# MINI_SAM_D51_004.net
KiCad netlist of a schematic drawn in EAGLE
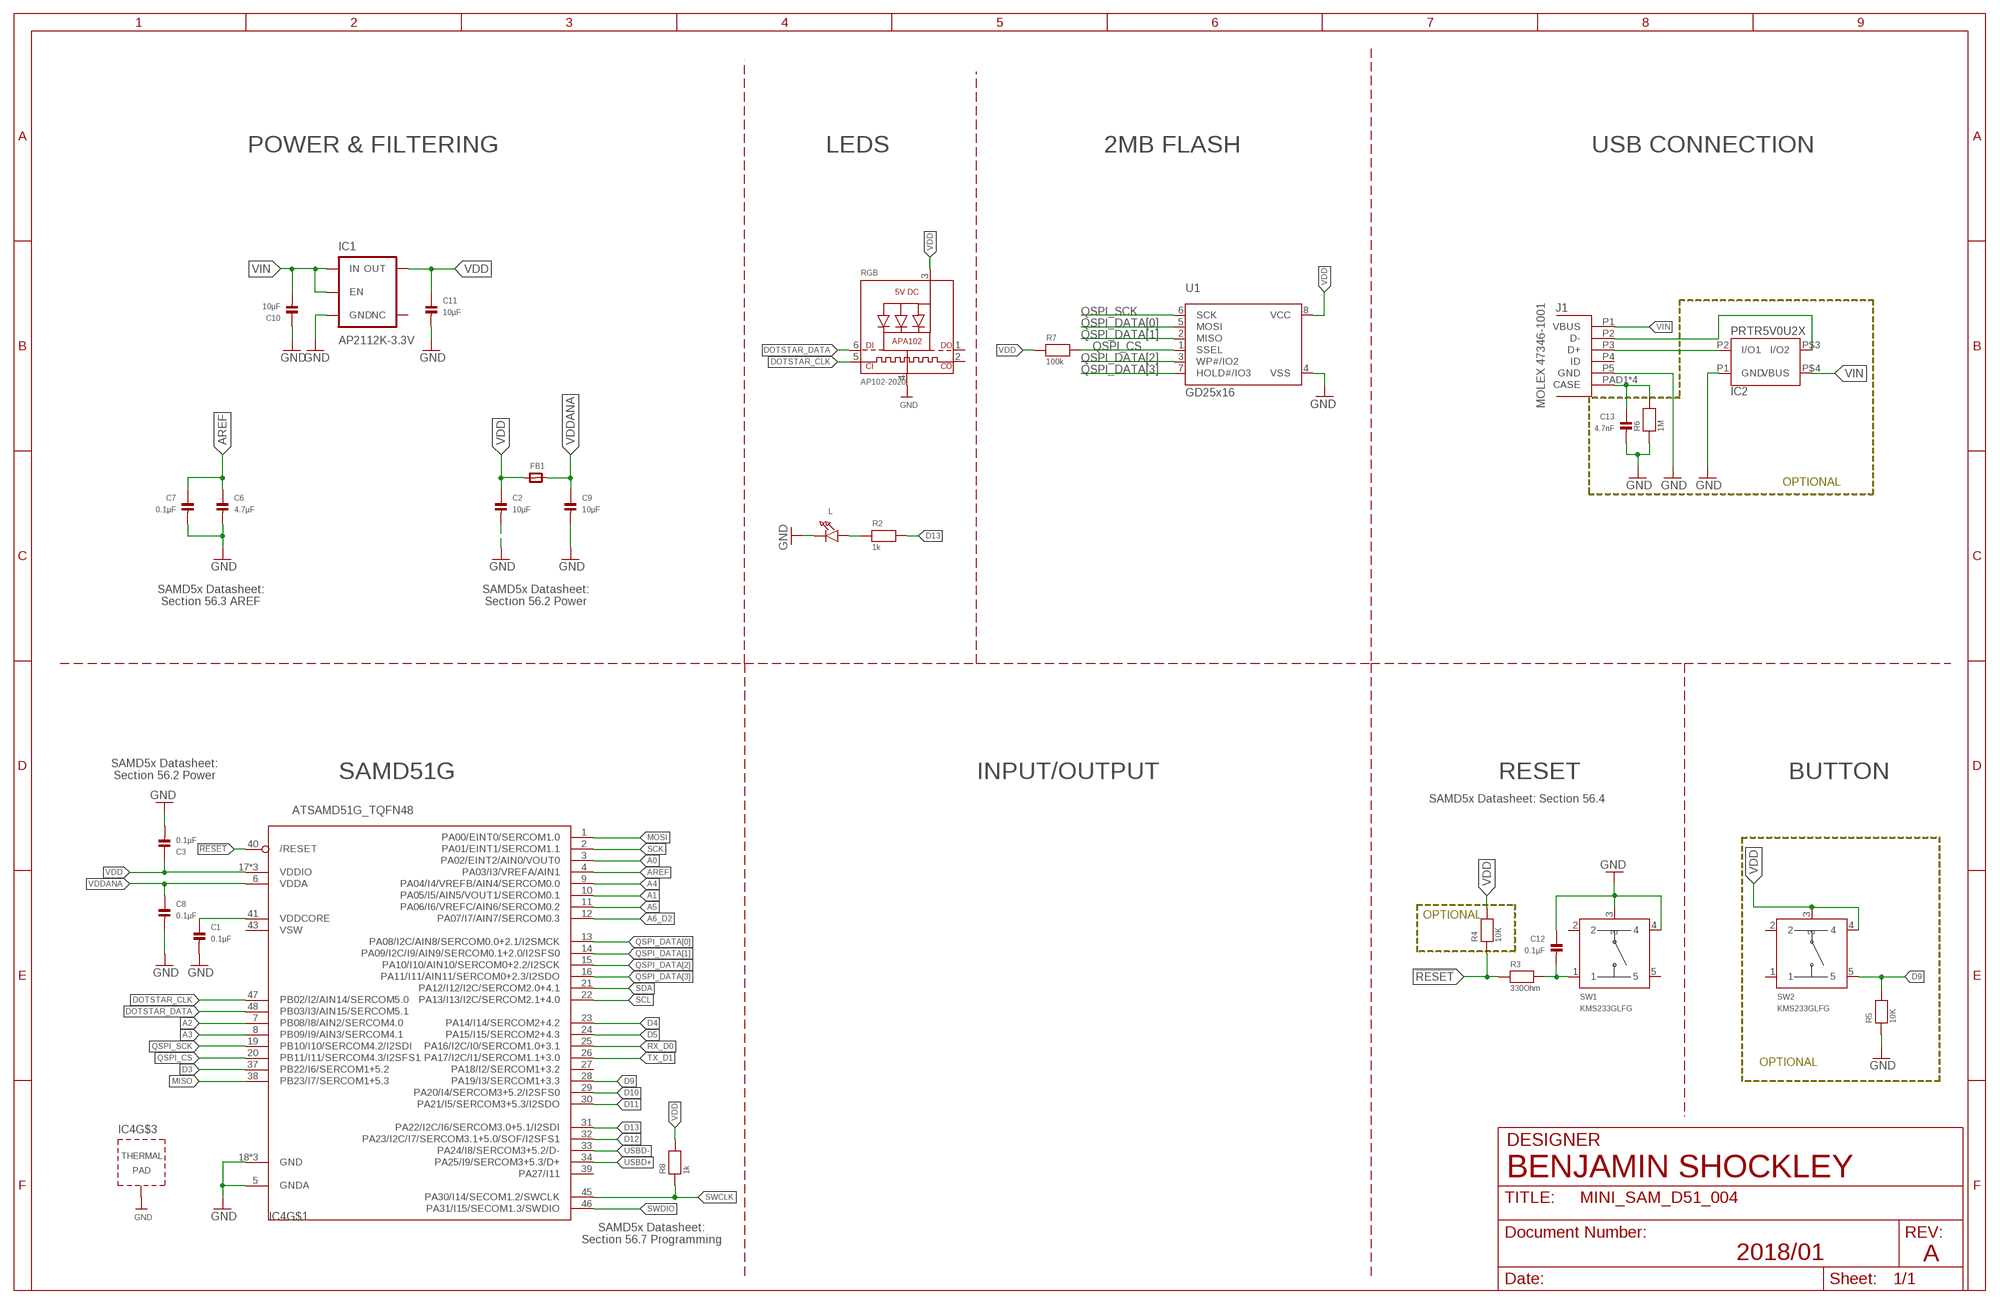
[diagram p0: schematic, sheet 1]

(export (version "E")
  (design (tool "Eeschema 10.0.6"))
  (components
    (comp (ref "C1")
      (value "0.1µF")
      (footprint "eagle-import:_0603MP")
      (libsource (lib "eagle-import") (part "CAP_CERAMIC_0603MP"))
    )
    (comp (ref "C2")
      (value "10µF")
      (footprint "eagle-import:_0603MP")
      (libsource (lib "eagle-import") (part "CAP_CERAMIC_0603MP"))
    )
    (comp (ref "C3")
      (value "0.1µF")
      (footprint "eagle-import:_0603MP")
      (libsource (lib "eagle-import") (part "CAP_CERAMIC_0603MP"))
    )
    (comp (ref "C6")
      (value "4.7µF")
      (footprint "eagle-import:_0603MP")
      (libsource (lib "eagle-import") (part "CAP_CERAMIC_0603MP"))
    )
    (comp (ref "C7")
      (value "0.1µF")
      (footprint "eagle-import:_0603MP")
      (libsource (lib "eagle-import") (part "CAP_CERAMIC_0603MP"))
    )
    (comp (ref "C8")
      (value "0.1µF")
      (footprint "eagle-import:_0603MP")
      (libsource (lib "eagle-import") (part "CAP_CERAMIC_0603MP"))
    )
    (comp (ref "C9")
      (value "10µF")
      (footprint "eagle-import:_0603MP")
      (libsource (lib "eagle-import") (part "CAP_CERAMIC_0603MP"))
    )
    (comp (ref "C10")
      (value "10µF")
      (footprint "eagle-import:_0603MP")
      (libsource (lib "eagle-import") (part "CAP_CERAMIC_0603MP"))
    )
    (comp (ref "C11")
      (value "10µF")
      (footprint "eagle-import:_0603MP")
      (libsource (lib "eagle-import") (part "CAP_CERAMIC_0603MP"))
    )
    (comp (ref "C12")
      (value "0.1µF")
      (footprint "eagle-import:_0603MP")
      (libsource (lib "eagle-import") (part "CAP_CERAMIC_0603MP"))
    )
    (comp (ref "C13")
      (value "4.7nF")
      (footprint "eagle-import:_0603MP")
      (libsource (lib "eagle-import") (part "CAP_CERAMIC_0603MP"))
    )
    (comp (ref "FB1")
      (value "FERRITE_0603MP")
      (footprint "eagle-import:_0603MP")
      (libsource (lib "eagle-import") (part "FERRITE_0603MP"))
    )
    (comp (ref "IC1")
      (value "AP2112K-3.3V")
      (footprint "eagle-import:SOT23-5")
      (libsource (lib "eagle-import") (part "V_REG_AP2112K-3.3V"))
    )
    (comp (ref "IC2")
      (value "PRTR5V0U2X")
      (footprint "eagle-import:SOT143B_REFLOW")
      (libsource (lib "eagle-import") (part "PRTR5V0U2X"))
    )
    (comp (ref "IC4")
      (value "ATSAMD51G_TQFN48")
      (footprint "eagle-import:TQFN48_7MM")
      (libsource (lib "eagle-import") (part "ATSAMD51G_TQFN48"))
    )
    (comp (ref "J1")
      (value "MOLEX_47346-100147346")
      (footprint "eagle-import:MOLEX_47346-1001")
      (libsource (lib "eagle-import") (part "MOLEX_47346-100147346"))
    )
    (comp (ref "L")
      (value "LED0603_NOOUTLINE")
      (footprint "eagle-import:CHIPLED_0603_NOOUTLINE")
      (libsource (lib "eagle-import") (part "LED0603_NOOUTLINE"))
    )
    (comp (ref "R2")
      (value "1k")
      (footprint "eagle-import:_0603MP")
      (libsource (lib "eagle-import") (part "RESISTOR_0603MP"))
    )
    (comp (ref "R3")
      (value "330Ohm")
      (footprint "eagle-import:_0603MP")
      (libsource (lib "eagle-import") (part "RESISTOR_0603MP"))
    )
    (comp (ref "R4")
      (value "10K")
      (footprint "eagle-import:_0603MP")
      (libsource (lib "eagle-import") (part "RESISTOR_0603MP"))
    )
    (comp (ref "R5")
      (value "10K")
      (footprint "eagle-import:_0603MP")
      (libsource (lib "eagle-import") (part "RESISTOR_0603MP"))
    )
    (comp (ref "R6")
      (value "1M")
      (footprint "eagle-import:_0603MP")
      (libsource (lib "eagle-import") (part "RESISTOR_0603MP"))
    )
    (comp (ref "R7")
      (value "100k")
      (footprint "eagle-import:_0603MP")
      (libsource (lib "eagle-import") (part "RESISTOR_0603MP"))
    )
    (comp (ref "R8")
      (value "1k")
      (footprint "eagle-import:_0603MP")
      (libsource (lib "eagle-import") (part "RESISTOR_0603MP"))
    )
    (comp (ref "RGB")
      (value "AP102-2020")
      (footprint "eagle-import:APA102_2020")
      (libsource (lib "eagle-import") (part "APA1022020"))
    )
    (comp (ref "SW1")
      (value "KMS233GLFG")
      (footprint "eagle-import:KMS_SWITCH")
      (libsource (lib "eagle-import") (part "KMS_SWITCHKMS"))
    )
    (comp (ref "SW2")
      (value "KMS233GLFG")
      (footprint "eagle-import:KMS_SWITCH")
      (libsource (lib "eagle-import") (part "KMS_SWITCHKMS"))
    )
    (comp (ref "U1")
      (value "GD25x16")
      (footprint "eagle-import:USON8")
      (libsource (lib "eagle-import") (part "SPIFLASH_8PINUX"))
    )
  )
  (nets
    (net (code "1") (name "/VSW") (class "Default")
      (node (ref "IC4") (pin "43") (pinfunction "VSW_43") (pintype "power_in"))
    )
    (net (code "2") (name "/~{RESET}") (class "Default")
      (node (ref "IC4") (pin "40") (pinfunction "/RESET_40") (pintype "bidirectional"))
      (node (ref "R3") (pin "1") (pinfunction "1_1") (pintype "passive"))
      (node (ref "R4") (pin "1") (pinfunction "1_1") (pintype "passive"))
    )
    (net (code "3") (name "A0") (class "Default")
      (node (ref "IC4") (pin "3") (pinfunction "PA02/EINT2/AIN0/VOUT0_3") (pintype "bidirectional"))
    )
    (net (code "4") (name "A1") (class "Default")
      (node (ref "IC4") (pin "10") (pinfunction "PA05/I5/AIN5/VOUT1/SERCOM0.1_10") (pintype "bidirectional"))
    )
    (net (code "5") (name "A2") (class "Default")
      (node (ref "IC4") (pin "7") (pinfunction "PB08/I8/AIN2/SERCOM4.0_7") (pintype "bidirectional"))
    )
    (net (code "6") (name "A3") (class "Default")
      (node (ref "IC4") (pin "8") (pinfunction "PB09/I9/AIN3/SERCOM4.1_8") (pintype "bidirectional"))
    )
    (net (code "7") (name "A4") (class "Default")
      (node (ref "IC4") (pin "9") (pinfunction "PA04/I4/VREFB/AIN4/SERCOM0.0_9") (pintype "bidirectional"))
    )
    (net (code "8") (name "A5") (class "Default")
      (node (ref "IC4") (pin "11") (pinfunction "PA06/I6/VREFC/AIN6/SERCOM0.2_11") (pintype "bidirectional"))
    )
    (net (code "9") (name "A6_D2") (class "Default")
      (node (ref "IC4") (pin "12") (pinfunction "PA07/I7/AIN7/SERCOM0.3_12") (pintype "bidirectional"))
    )
    (net (code "10") (name "AREF") (class "Default")
      (node (ref "C6") (pin "1") (pinfunction "P$1_1") (pintype "passive"))
      (node (ref "C7") (pin "1") (pinfunction "P$1_1") (pintype "passive"))
      (node (ref "IC4") (pin "4") (pinfunction "PA03/I3/VREFA/AIN1_4") (pintype "bidirectional"))
    )
    (net (code "11") (name "D3") (class "Default")
      (node (ref "IC4") (pin "37") (pinfunction "PB22/I6/SERCOM1+5.2_37") (pintype "bidirectional"))
    )
    (net (code "12") (name "D4") (class "Default")
      (node (ref "IC4") (pin "23") (pinfunction "PA14/I14/SERCOM2+4.2_23") (pintype "bidirectional"))
    )
    (net (code "13") (name "D5") (class "Default")
      (node (ref "IC4") (pin "24") (pinfunction "PA15/I15/SERCOM2+4.3_24") (pintype "bidirectional"))
    )
    (net (code "14") (name "D9") (class "Default")
      (node (ref "IC4") (pin "28") (pinfunction "PA19/I3/SERCOM1+3.3_28") (pintype "bidirectional"))
      (node (ref "R5") (pin "2") (pinfunction "2_2") (pintype "passive"))
      (node (ref "SW2") (pin "5") (pinfunction "5_5") (pintype "bidirectional"))
    )
    (net (code "15") (name "D10") (class "Default")
      (node (ref "IC4") (pin "29") (pinfunction "PA20/I4/SERCOM3+5.2/I2SFS0_29") (pintype "bidirectional"))
    )
    (net (code "16") (name "D11") (class "Default")
      (node (ref "IC4") (pin "30") (pinfunction "PA21/I5/SERCOM3+5.3/I2SDO_30") (pintype "bidirectional"))
    )
    (net (code "17") (name "D12") (class "Default")
      (node (ref "IC4") (pin "32") (pinfunction "PA23/I2C/I7/SERCOM3.1+5.0/SOF/I2SFS1_32") (pintype "bidirectional"))
    )
    (net (code "18") (name "D13") (class "Default")
      (node (ref "IC4") (pin "31") (pinfunction "PA22/I2C/I6/SERCOM3.0+5.1/I2SDI_31") (pintype "bidirectional"))
      (node (ref "R2") (pin "2") (pinfunction "2_2") (pintype "passive"))
    )
    (net (code "19") (name "DOTSTAR_CLK") (class "Default")
      (node (ref "IC4") (pin "47") (pinfunction "PB02/I2/AIN14/SERCOM5.0_47") (pintype "bidirectional"))
      (node (ref "RGB") (pin "5") (pinfunction "CKI_5") (pintype "input"))
    )
    (net (code "20") (name "DOTSTAR_DATA") (class "Default")
      (node (ref "IC4") (pin "48") (pinfunction "PB03/I3/AIN15/SERCOM5.1_48") (pintype "bidirectional"))
      (node (ref "RGB") (pin "6") (pinfunction "DI_6") (pintype "input"))
    )
    (net (code "21") (name "GND") (class "Default")
      (node (ref "C1") (pin "2") (pinfunction "P$2_2") (pintype "passive"))
      (node (ref "C10") (pin "1") (pinfunction "P$1_1") (pintype "passive"))
      (node (ref "C11") (pin "2") (pinfunction "P$2_2") (pintype "passive"))
      (node (ref "C12") (pin "1") (pinfunction "P$1_1") (pintype "passive"))
      (node (ref "C13") (pin "2") (pinfunction "P$2_2") (pintype "passive"))
      (node (ref "C2") (pin "2") (pinfunction "P$2_2") (pintype "passive"))
      (node (ref "C3") (pin "2") (pinfunction "P$2_2") (pintype "passive"))
      (node (ref "C6") (pin "2") (pinfunction "P$2_2") (pintype "passive"))
      (node (ref "C7") (pin "2") (pinfunction "P$2_2") (pintype "passive"))
      (node (ref "C8") (pin "2") (pinfunction "P$2_2") (pintype "passive"))
      (node (ref "C9") (pin "2") (pinfunction "P$2_2") (pintype "passive"))
      (node (ref "IC1") (pin "2") (pinfunction "GND_2") (pintype "input"))
      (node (ref "IC2") (pin "P1") (pinfunction "GND_P1") (pintype "bidirectional"))
      (node (ref "IC4") (pin "18") (pinfunction "GND_18") (pintype "power_in"))
      (node (ref "IC4") (pin "35") (pinfunction "GND_35") (pintype "power_in"))
      (node (ref "IC4") (pin "42") (pinfunction "GND_42") (pintype "power_in"))
      (node (ref "IC4") (pin "5") (pinfunction "GNDA_5") (pintype "power_in"))
      (node (ref "IC4") (pin "THERMAL") (pinfunction "TP_THERMAL") (pintype "power_in"))
      (node (ref "J1") (pin "P5") (pinfunction "GND_P5") (pintype "power_in"))
      (node (ref "L") (pin "C") (pinfunction "C_C") (pintype "passive"))
      (node (ref "R5") (pin "1") (pinfunction "1_1") (pintype "passive"))
      (node (ref "R6") (pin "1") (pinfunction "1_1") (pintype "passive"))
      (node (ref "RGB") (pin "4") (pinfunction "GND_4") (pintype "power_in"))
      (node (ref "SW1") (pin "3") (pinfunction "3_3") (pintype "bidirectional"))
      (node (ref "SW1") (pin "4") (pinfunction "4_4") (pintype "bidirectional"))
      (node (ref "U1") (pin "4") (pinfunction "VSS_4") (pintype "bidirectional"))
    )
    (net (code "22") (name "MISO") (class "Default")
      (node (ref "IC4") (pin "38") (pinfunction "PB23/I7/SERCOM1+5.3_38") (pintype "bidirectional"))
    )
    (net (code "23") (name "MOSI") (class "Default")
      (node (ref "IC4") (pin "1") (pinfunction "PA00/EINT0/SERCOM1.0_1") (pintype "bidirectional"))
    )
    (net (code "24") (name "Net-(C1-P$1)") (class "Default")
      (node (ref "C1") (pin "1") (pinfunction "P$1_1") (pintype "passive"))
      (node (ref "IC4") (pin "41") (pinfunction "VDDCORE_41") (pintype "power_in"))
    )
    (net (code "25") (name "Net-(C12-P$2)") (class "Default")
      (node (ref "C12") (pin "2") (pinfunction "P$2_2") (pintype "passive"))
      (node (ref "R3") (pin "2") (pinfunction "2_2") (pintype "passive"))
      (node (ref "SW1") (pin "1") (pinfunction "1_1") (pintype "bidirectional"))
    )
    (net (code "26") (name "Net-(C13-P$1)") (class "Default")
      (node (ref "C13") (pin "1") (pinfunction "P$1_1") (pintype "passive"))
      (node (ref "J1") (pin "PAD1") (pinfunction "CASE_PAD1") (pintype "bidirectional"))
      (node (ref "J1") (pin "PAD2") (pinfunction "CASE_PAD2") (pintype "bidirectional"))
      (node (ref "J1") (pin "PAD3") (pinfunction "CASE_PAD3") (pintype "bidirectional"))
      (node (ref "J1") (pin "PAD4") (pinfunction "CASE_PAD4") (pintype "bidirectional"))
      (node (ref "R6") (pin "2") (pinfunction "2_2") (pintype "passive"))
    )
    (net (code "27") (name "Net-(L-PadA)") (class "Default")
      (node (ref "L") (pin "A") (pinfunction "A_A") (pintype "passive"))
      (node (ref "R2") (pin "1") (pinfunction "1_1") (pintype "passive"))
    )
    (net (code "28") (name "QSPI_CS") (class "Default")
      (node (ref "IC4") (pin "20") (pinfunction "PB11/I11/SERCOM4.3/I2SFS1_20") (pintype "bidirectional"))
      (node (ref "R7") (pin "2") (pinfunction "2_2") (pintype "passive"))
      (node (ref "U1") (pin "1") (pinfunction "SSEL_1") (pintype "bidirectional"))
    )
    (net (code "29") (name "QSPI_DATA[0]") (class "Default")
      (node (ref "IC4") (pin "13") (pinfunction "PA08/I2C/AIN8/SERCOM0.0+2.1/I2SMCK_13") (pintype "bidirectional"))
      (node (ref "U1") (pin "5") (pinfunction "MOSI_5") (pintype "bidirectional"))
    )
    (net (code "30") (name "QSPI_DATA[1]") (class "Default")
      (node (ref "IC4") (pin "14") (pinfunction "PA09/I2C/I9/AIN9/SERCOM0.1+2.0/I2SFS0_14") (pintype "bidirectional"))
      (node (ref "U1") (pin "2") (pinfunction "MISO_2") (pintype "bidirectional"))
    )
    (net (code "31") (name "QSPI_DATA[2]") (class "Default")
      (node (ref "IC4") (pin "15") (pinfunction "PA10/I10/AIN10/SERCOM0+2.2/I2SCK_15") (pintype "bidirectional"))
      (node (ref "U1") (pin "3") (pinfunction "WP#/IO2_3") (pintype "bidirectional"))
    )
    (net (code "32") (name "QSPI_DATA[3]") (class "Default")
      (node (ref "IC4") (pin "16") (pinfunction "PA11/I11/AIN11/SERCOM0+2.3/I2SDO_16") (pintype "bidirectional"))
      (node (ref "U1") (pin "7") (pinfunction "HOLD#/IO3_7") (pintype "bidirectional"))
    )
    (net (code "33") (name "QSPI_SCK") (class "Default")
      (node (ref "IC4") (pin "19") (pinfunction "PB10/I10/SERCOM4.2/I2SDI_19") (pintype "bidirectional"))
      (node (ref "U1") (pin "6") (pinfunction "SCK_6") (pintype "bidirectional"))
    )
    (net (code "34") (name "RX_D0") (class "Default")
      (node (ref "IC4") (pin "25") (pinfunction "PA16/I2C/I0/SERCOM1.0+3.1_25") (pintype "bidirectional"))
    )
    (net (code "35") (name "SCK") (class "Default")
      (node (ref "IC4") (pin "2") (pinfunction "PA01/EINT1/SERCOM1.1_2") (pintype "bidirectional"))
    )
    (net (code "36") (name "SCL") (class "Default")
      (node (ref "IC4") (pin "22") (pinfunction "PA13/I13/I2C/SERCOM2.1+4.0_22") (pintype "bidirectional"))
    )
    (net (code "37") (name "SDA") (class "Default")
      (node (ref "IC4") (pin "21") (pinfunction "PA12/I12/I2C/SERCOM2.0+4.1_21") (pintype "bidirectional"))
    )
    (net (code "38") (name "SWCLK") (class "Default")
      (node (ref "IC4") (pin "45") (pinfunction "PA30/I14/SECOM1.2/SWCLK_45") (pintype "bidirectional"))
      (node (ref "R8") (pin "1") (pinfunction "1_1") (pintype "passive"))
    )
    (net (code "39") (name "SWDIO") (class "Default")
      (node (ref "IC4") (pin "46") (pinfunction "PA31/I15/SECOM1.3/SWDIO_46") (pintype "bidirectional"))
    )
    (net (code "40") (name "TX_D1") (class "Default")
      (node (ref "IC4") (pin "26") (pinfunction "PA17/I2C/I1/SERCOM1.1+3.0_26") (pintype "bidirectional"))
    )
    (net (code "41") (name "USBD+") (class "Default")
      (node (ref "IC2") (pin "P2") (pinfunction "I/O1_P2") (pintype "bidirectional"))
      (node (ref "IC4") (pin "34") (pinfunction "PA25/I9/SERCOM3+5.3/D+_34") (pintype "bidirectional"))
      (node (ref "J1") (pin "P3") (pinfunction "D+_P3") (pintype "bidirectional"))
    )
    (net (code "42") (name "USBD-") (class "Default")
      (node (ref "IC2") (pin "P$3") (pinfunction "I/O2_P$3") (pintype "bidirectional"))
      (node (ref "IC4") (pin "33") (pinfunction "PA24/I8/SERCOM3+5.2/D-_33") (pintype "bidirectional"))
      (node (ref "J1") (pin "P2") (pinfunction "D-_P2") (pintype "bidirectional"))
    )
    (net (code "43") (name "VDD") (class "Default")
      (node (ref "C11") (pin "1") (pinfunction "P$1_1") (pintype "passive"))
      (node (ref "C2") (pin "1") (pinfunction "P$1_1") (pintype "passive"))
      (node (ref "C3") (pin "1") (pinfunction "P$1_1") (pintype "passive"))
      (node (ref "FB1") (pin "1") (pinfunction "P$1_1") (pintype "passive"))
      (node (ref "IC1") (pin "5") (pinfunction "OUT_5") (pintype "passive"))
      (node (ref "IC4") (pin "17") (pinfunction "VDDIO_17") (pintype "power_in"))
      (node (ref "IC4") (pin "36") (pinfunction "VDDIO_36") (pintype "power_in"))
      (node (ref "IC4") (pin "44") (pinfunction "VDDIO_44") (pintype "power_in"))
      (node (ref "R4") (pin "2") (pinfunction "2_2") (pintype "passive"))
      (node (ref "R7") (pin "1") (pinfunction "1_1") (pintype "passive"))
      (node (ref "R8") (pin "2") (pinfunction "2_2") (pintype "passive"))
      (node (ref "RGB") (pin "3") (pinfunction "VDD_3") (pintype "power_in"))
      (node (ref "SW2") (pin "3") (pinfunction "3_3") (pintype "bidirectional"))
      (node (ref "SW2") (pin "4") (pinfunction "4_4") (pintype "bidirectional"))
      (node (ref "U1") (pin "8") (pinfunction "VCC_8") (pintype "bidirectional"))
    )
    (net (code "44") (name "VDDANA") (class "Default")
      (node (ref "C8") (pin "1") (pinfunction "P$1_1") (pintype "passive"))
      (node (ref "C9") (pin "1") (pinfunction "P$1_1") (pintype "passive"))
      (node (ref "FB1") (pin "2") (pinfunction "P$2_2") (pintype "passive"))
      (node (ref "IC4") (pin "6") (pinfunction "VDDA_6") (pintype "power_in"))
    )
    (net (code "45") (name "VIN") (class "Default")
      (node (ref "C10") (pin "2") (pinfunction "P$2_2") (pintype "passive"))
      (node (ref "IC1") (pin "1") (pinfunction "IN_1") (pintype "input"))
      (node (ref "IC1") (pin "3") (pinfunction "EN_3") (pintype "input"))
      (node (ref "IC2") (pin "P$4") (pinfunction "VBUS_P$4") (pintype "bidirectional"))
      (node (ref "J1") (pin "P1") (pinfunction "VBUS_P1") (pintype "power_in"))
    )
    (net (code "46") (name "unconnected-(IC1-NC-Pad4)") (class "Default")
      (node (ref "IC1") (pin "4") (pinfunction "NC_4") (pintype "input"))
    )
    (net (code "47") (name "unconnected-(IC4A-PA18{slash}I2{slash}SERCOM1+3.2-Pad27)") (class "Default")
      (node (ref "IC4") (pin "27") (pinfunction "PA18/I2/SERCOM1+3.2_27") (pintype "bidirectional"))
    )
    (net (code "48") (name "unconnected-(IC4A-PA27{slash}I11-Pad39)") (class "Default")
      (node (ref "IC4") (pin "39") (pinfunction "PA27/I11_39") (pintype "bidirectional"))
    )
    (net (code "49") (name "unconnected-(J1-ID-PadP4)") (class "Default")
      (node (ref "J1") (pin "P4") (pinfunction "ID_P4") (pintype "bidirectional"))
    )
    (net (code "50") (name "unconnected-(RGB-CKO-Pad2)") (class "Default")
      (node (ref "RGB") (pin "2") (pinfunction "CKO_2") (pintype "output"))
    )
    (net (code "51") (name "unconnected-(RGB-DO-Pad1)") (class "Default")
      (node (ref "RGB") (pin "1") (pinfunction "DO_1") (pintype "output"))
    )
    (net (code "52") (name "unconnected-(SW1-Pad2)") (class "Default")
      (node (ref "SW1") (pin "2") (pinfunction "2_2") (pintype "bidirectional"))
    )
    (net (code "53") (name "unconnected-(SW1-Pad5)") (class "Default")
      (node (ref "SW1") (pin "5") (pinfunction "5_5") (pintype "bidirectional"))
    )
    (net (code "54") (name "unconnected-(SW2-Pad1)") (class "Default")
      (node (ref "SW2") (pin "1") (pinfunction "1_1") (pintype "bidirectional"))
    )
    (net (code "55") (name "unconnected-(SW2-Pad2)") (class "Default")
      (node (ref "SW2") (pin "2") (pinfunction "2_2") (pintype "bidirectional"))
    )
  )
)
